# AS32.net
KiCad netlist of a schematic drawn in EAGLE
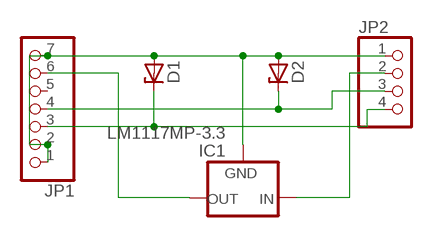
[diagram p0: schematic, sheet 1]

(export (version "E")
  (design (tool "Eeschema 10.0.6"))
  (components
    (comp (ref "D1")
      (value "ZENER-DIODEDO35Z10")
      (footprint "eagle-import:DO35Z10")
      (libsource (lib "eagle-import") (part "ZENER-DIODEDO35Z10"))
    )
    (comp (ref "D2")
      (value "ZENER-DIODEDO35Z10")
      (footprint "eagle-import:DO35Z10")
      (libsource (lib "eagle-import") (part "ZENER-DIODEDO35Z10"))
    )
    (comp (ref "IC1")
      (value "LM1117MP-3.3")
      (footprint "eagle-import:SOT223")
      (fields (field (name "MF") "Texas Instruments"))
      (libsource (lib "eagle-import") (part "LM1117?-MP3.3"))
    )
    (comp (ref "JP1")
      (value "PINHD-1X7")
      (footprint "eagle-import:1X07")
      (libsource (lib "eagle-import") (part "PINHD-1X7"))
    )
    (comp (ref "JP2")
      (value "PINHD-1X4")
      (footprint "eagle-import:1X04")
      (libsource (lib "eagle-import") (part "PINHD-1X4"))
    )
  )
  (nets
    (net (code "1") (name "Net-(D1-PadC)") (class "Default")
      (node (ref "D1") (pin "C") (pinfunction "C_C") (pintype "passive"))
      (node (ref "JP1") (pin "3") (pinfunction "3_3") (pintype "passive"))
      (node (ref "JP2") (pin "4") (pinfunction "4_4") (pintype "passive"))
    )
    (net (code "2") (name "Net-(D2-PadC)") (class "Default")
      (node (ref "D2") (pin "C") (pinfunction "C_C") (pintype "passive"))
      (node (ref "JP1") (pin "4") (pinfunction "4_4") (pintype "passive"))
      (node (ref "JP2") (pin "3") (pinfunction "3_3") (pintype "passive"))
    )
    (net (code "3") (name "Net-(IC1-GND)") (class "Default")
      (node (ref "D1") (pin "A") (pinfunction "A_A") (pintype "passive"))
      (node (ref "D2") (pin "A") (pinfunction "A_A") (pintype "passive"))
      (node (ref "IC1") (pin "1") (pinfunction "GND_1") (pintype "input"))
      (node (ref "JP1") (pin "1") (pinfunction "1_1") (pintype "passive"))
      (node (ref "JP1") (pin "2") (pinfunction "2_2") (pintype "passive"))
      (node (ref "JP1") (pin "7") (pinfunction "7_7") (pintype "passive"))
      (node (ref "JP2") (pin "1") (pinfunction "1_1") (pintype "passive"))
    )
    (net (code "4") (name "Net-(IC1-IN)") (class "Default")
      (node (ref "IC1") (pin "3") (pinfunction "IN_3") (pintype "input"))
      (node (ref "JP2") (pin "2") (pinfunction "2_2") (pintype "passive"))
    )
    (net (code "5") (name "Net-(IC1-OUT-Pad2)") (class "Default")
      (node (ref "IC1") (pin "2") (pinfunction "OUT_2") (pintype "passive"))
      (node (ref "IC1") (pin "4") (pinfunction "OUT_4") (pintype "passive"))
      (node (ref "JP1") (pin "6") (pinfunction "6_6") (pintype "passive"))
    )
    (net (code "6") (name "unconnected-(JP1-Pad5)") (class "Default")
      (node (ref "JP1") (pin "5") (pinfunction "5_5") (pintype "passive"))
    )
  )
)
